# Other.net
KiCad netlist of a schematic drawn in Altium Designer
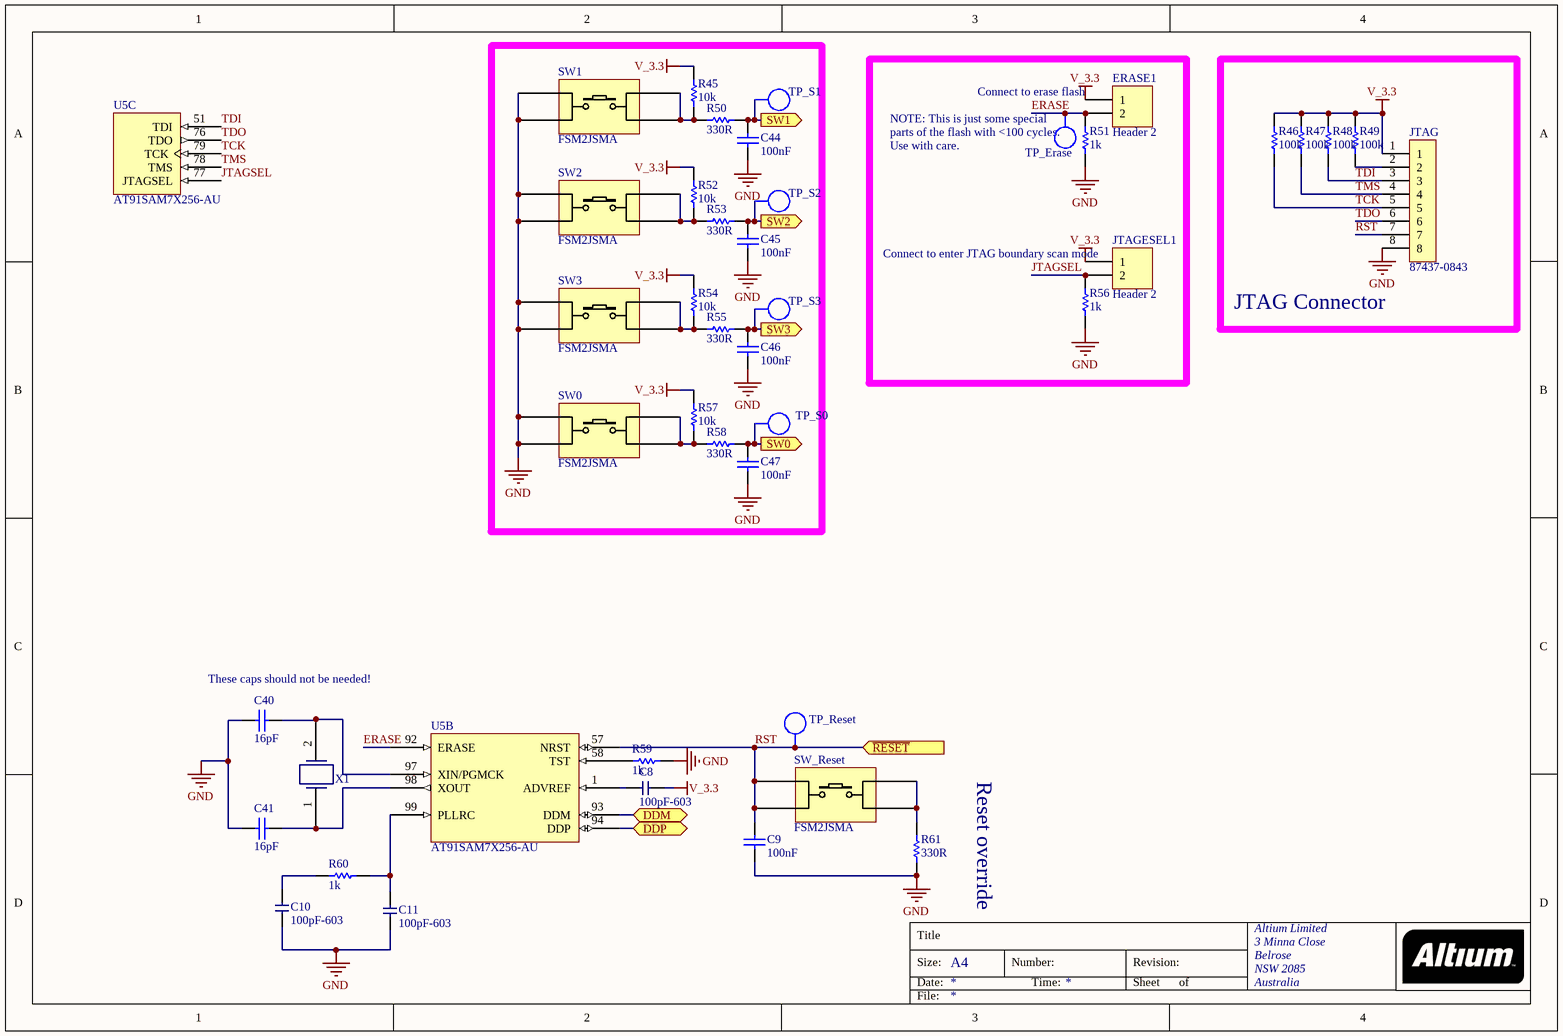
[diagram p0: Other.SchDoc]

(export (version "E")
  (design (tool "Eeschema 10.0.6"))
  (components
    (comp (ref "C8")
      (value "100pF-603")
      (footprint "0603 Resistor")
      (fields
        (field (name "MANUFACTURER PART NUMBER") "06035A101JAT2A")
        (field (name "MANUFACTURER") "AVX Corporation")
      )
      (libsource (lib "MarioLib") (part "100pF-603"))
    )
    (comp (ref "C9")
      (value "100nF")
      (footprint "0603")
      (description "CAP CER .10UF 50V X5R 0603")
      (fields (field (name "PART NUMBER") "CP_100nF 0603") (field (name "MANUFACTURER") "Taiyo Yuden"))
      (libsource (lib "ENEL429_4") (part "CP_100nF 0603"))
    )
    (comp (ref "C10")
      (value "100pF-603")
      (footprint "0603 Resistor")
      (fields
        (field (name "MANUFACTURER PART NUMBER") "06035A101JAT2A")
        (field (name "MANUFACTURER") "AVX Corporation")
      )
      (libsource (lib "MarioLib") (part "100pF-603"))
    )
    (comp (ref "C11")
      (value "100pF-603")
      (footprint "0603 Resistor")
      (fields
        (field (name "MANUFACTURER PART NUMBER") "06035A101JAT2A")
        (field (name "MANUFACTURER") "AVX Corporation")
      )
      (libsource (lib "MarioLib") (part "100pF-603"))
    )
    (comp (ref "C40")
      (value "16pF")
      (footprint "0603")
      (description "CAP CER 16PF 100V 5% C0G 0603")
      (fields (field (name "MANUFACTURER") "Murata") (field (name "PART NUMBER") "CP_16pF_100V_0603"))
      (libsource (lib "ENEL429_4") (part "CP_16pF_100V_0603"))
    )
    (comp (ref "C41")
      (value "16pF")
      (footprint "0603")
      (description "CAP CER 16PF 100V 5% C0G 0603")
      (fields (field (name "MANUFACTURER") "Murata") (field (name "PART NUMBER") "CP_16pF_100V_0603"))
      (libsource (lib "ENEL429_4") (part "CP_16pF_100V_0603"))
    )
    (comp (ref "C44")
      (value "100nF")
      (footprint "0603")
      (description "CAP CER .10UF 50V X5R 0603")
      (fields (field (name "MANUFACTURER") "Taiyo Yuden") (field (name "PART NUMBER") "CP_100nF 0603"))
      (libsource (lib "ENEL429_4") (part "CP_100nF 0603"))
    )
    (comp (ref "C45")
      (value "100nF")
      (footprint "0603")
      (description "CAP CER .10UF 50V X5R 0603")
      (fields (field (name "MANUFACTURER") "Taiyo Yuden") (field (name "PART NUMBER") "CP_100nF 0603"))
      (libsource (lib "ENEL429_4") (part "CP_100nF 0603"))
    )
    (comp (ref "C46")
      (value "100nF")
      (footprint "0603")
      (description "CAP CER .10UF 50V X5R 0603")
      (fields (field (name "MANUFACTURER") "Taiyo Yuden") (field (name "PART NUMBER") "CP_100nF 0603"))
      (libsource (lib "ENEL429_4") (part "CP_100nF 0603"))
    )
    (comp (ref "C47")
      (value "100nF")
      (footprint "0603")
      (description "CAP CER .10UF 50V X5R 0603")
      (fields (field (name "MANUFACTURER") "Taiyo Yuden") (field (name "PART NUMBER") "CP_100nF 0603"))
      (libsource (lib "ENEL429_4") (part "CP_100nF 0603"))
    )
    (comp (ref "ERASE1")
      (value "Header 2")
      (footprint "HDR1X2")
      (description "Header, 2-Pin")
      (fields (field (name "PUBLISHER") "Altium Limited"))
      (libsource (lib "Miscellaneous Connectors") (part "Header 2"))
    )
    (comp (ref "JTAG")
      (value "87437-0843")
      (footprint "87437-0843")
      (fields (field (name "MANUFACTURER") "Molex"))
      (libsource (lib "MarioLib") (part "87437-0843"))
    )
    (comp (ref "JTAGESEL1")
      (value "Header 2")
      (footprint "HDR1X2")
      (description "Header, 2-Pin")
      (fields (field (name "PUBLISHER") "Altium Limited"))
      (libsource (lib "Miscellaneous Connectors") (part "Header 2"))
    )
    (comp (ref "R45")
      (value "10k")
      (footprint "0603")
      (description "RES 10.0K OHM 1/10W 1% 0603 SMD")
      (fields (field (name "MANUFACTURER") "Yageo") (field (name "PART NUMBER") "RS_10k 0603"))
      (libsource (lib "ENEL429_4") (part "RS_10k 0603"))
    )
    (comp (ref "R46")
      (value "100k")
      (footprint "0603")
      (description "RES 100K OHM 1/10W 1% 0603 SMD")
      (fields (field (name "PART NUMBER") "RS_100k 0603") (field (name "MANUFACTURER") "Yageo"))
      (libsource (lib "ENEL429_4") (part "RS_100k 0603"))
    )
    (comp (ref "R47")
      (value "100k")
      (footprint "0603")
      (description "RES 100K OHM 1/10W 1% 0603 SMD")
      (fields (field (name "PART NUMBER") "RS_100k 0603") (field (name "MANUFACTURER") "Yageo"))
      (libsource (lib "ENEL429_4") (part "RS_100k 0603"))
    )
    (comp (ref "R48")
      (value "100k")
      (footprint "0603")
      (description "RES 100K OHM 1/10W 1% 0603 SMD")
      (fields (field (name "PART NUMBER") "RS_100k 0603") (field (name "MANUFACTURER") "Yageo"))
      (libsource (lib "ENEL429_4") (part "RS_100k 0603"))
    )
    (comp (ref "R49")
      (value "100k")
      (footprint "0603")
      (description "RES 100K OHM 1/10W 1% 0603 SMD")
      (fields (field (name "PART NUMBER") "RS_100k 0603") (field (name "MANUFACTURER") "Yageo"))
      (libsource (lib "ENEL429_4") (part "RS_100k 0603"))
    )
    (comp (ref "R50")
      (value "330R")
      (footprint "0603")
      (description "RES 330 OHM 1/10W 1% 0603 SMD")
      (fields (field (name "MANUFACTURER") "Yageo") (field (name "PART NUMBER") "RS_330R 0603"))
      (libsource (lib "ENEL429_4") (part "RS_330R 0603"))
    )
    (comp (ref "R51")
      (value "1k")
      (footprint "0603")
      (description "RES 1.00K OHM 1/10W 1% 0603 SMD")
      (fields (field (name "PART NUMBER") "RS_1k 0603") (field (name "MANUFACTURER") "ROHM"))
      (libsource (lib "ENEL429_4") (part "RS_1k 0603"))
    )
    (comp (ref "R52")
      (value "10k")
      (footprint "0603")
      (description "RES 10.0K OHM 1/10W 1% 0603 SMD")
      (fields (field (name "MANUFACTURER") "Yageo") (field (name "PART NUMBER") "RS_10k 0603"))
      (libsource (lib "ENEL429_4") (part "RS_10k 0603"))
    )
    (comp (ref "R53")
      (value "330R")
      (footprint "0603")
      (description "RES 330 OHM 1/10W 1% 0603 SMD")
      (fields (field (name "MANUFACTURER") "Yageo") (field (name "PART NUMBER") "RS_330R 0603"))
      (libsource (lib "ENEL429_4") (part "RS_330R 0603"))
    )
    (comp (ref "R54")
      (value "10k")
      (footprint "0603")
      (description "RES 10.0K OHM 1/10W 1% 0603 SMD")
      (fields (field (name "MANUFACTURER") "Yageo") (field (name "PART NUMBER") "RS_10k 0603"))
      (libsource (lib "ENEL429_4") (part "RS_10k 0603"))
    )
    (comp (ref "R55")
      (value "330R")
      (footprint "0603")
      (description "RES 330 OHM 1/10W 1% 0603 SMD")
      (fields (field (name "MANUFACTURER") "Yageo") (field (name "PART NUMBER") "RS_330R 0603"))
      (libsource (lib "ENEL429_4") (part "RS_330R 0603"))
    )
    (comp (ref "R56")
      (value "1k")
      (footprint "0603")
      (description "RES 1.00K OHM 1/10W 1% 0603 SMD")
      (fields (field (name "PART NUMBER") "RS_1k 0603") (field (name "MANUFACTURER") "ROHM"))
      (libsource (lib "ENEL429_4") (part "RS_1k 0603"))
    )
    (comp (ref "R57")
      (value "10k")
      (footprint "0603")
      (description "RES 10.0K OHM 1/10W 1% 0603 SMD")
      (fields (field (name "MANUFACTURER") "Yageo") (field (name "PART NUMBER") "RS_10k 0603"))
      (libsource (lib "ENEL429_4") (part "RS_10k 0603"))
    )
    (comp (ref "R58")
      (value "330R")
      (footprint "0603")
      (description "RES 330 OHM 1/10W 1% 0603 SMD")
      (fields (field (name "MANUFACTURER") "Yageo") (field (name "PART NUMBER") "RS_330R 0603"))
      (libsource (lib "ENEL429_4") (part "RS_330R 0603"))
    )
    (comp (ref "R59")
      (value "1k")
      (footprint "0603")
      (description "RES 1.00K OHM 1/10W 1% 0603 SMD")
      (fields (field (name "PART NUMBER") "RS_1k 0603") (field (name "MANUFACTURER") "ROHM"))
      (libsource (lib "ENEL429_4") (part "RS_1k 0603"))
    )
    (comp (ref "R60")
      (value "1k")
      (footprint "0603")
      (description "RES 1.00K OHM 1/10W 1% 0603 SMD")
      (fields (field (name "MANUFACTURER") "ROHM") (field (name "PART NUMBER") "RS_1k 0603"))
      (libsource (lib "ENEL429_4") (part "RS_1k 0603"))
    )
    (comp (ref "R61")
      (value "330R")
      (footprint "0603")
      (description "RES 330 OHM 1/10W 1% 0603 SMD")
      (fields (field (name "PART NUMBER") "RS_330R 0603") (field (name "MANUFACTURER") "Yageo"))
      (libsource (lib "ENEL429_4") (part "RS_330R 0603"))
    )
    (comp (ref "SW0")
      (value "FSM2JSMA")
      (footprint "FSM2JSMA")
      (description "DPST SMD Switch")
      (fields (field (name "MANUFACTURER") "Tyco Electronics") (field (name "PART NUMBER") "SW_FSM2JSMA"))
      (libsource (lib "ENEL429_4") (part "SW_FSM2JSMA"))
    )
    (comp (ref "SW1")
      (value "FSM2JSMA")
      (footprint "FSM2JSMA")
      (description "DPST SMD Switch")
      (fields (field (name "MANUFACTURER") "Tyco Electronics") (field (name "PART NUMBER") "SW_FSM2JSMA"))
      (libsource (lib "ENEL429_4") (part "SW_FSM2JSMA"))
    )
    (comp (ref "SW2")
      (value "FSM2JSMA")
      (footprint "FSM2JSMA")
      (description "DPST SMD Switch")
      (fields (field (name "MANUFACTURER") "Tyco Electronics") (field (name "PART NUMBER") "SW_FSM2JSMA"))
      (libsource (lib "ENEL429_4") (part "SW_FSM2JSMA"))
    )
    (comp (ref "SW3")
      (value "FSM2JSMA")
      (footprint "FSM2JSMA")
      (description "DPST SMD Switch")
      (fields (field (name "MANUFACTURER") "Tyco Electronics") (field (name "PART NUMBER") "SW_FSM2JSMA"))
      (libsource (lib "ENEL429_4") (part "SW_FSM2JSMA"))
    )
    (comp (ref "SW_Reset")
      (value "FSM2JSMA")
      (footprint "FSM2JSMA")
      (description "DPST SMD Switch")
      (fields (field (name "MANUFACTURER") "Tyco Electronics") (field (name "PART NUMBER") "SW_FSM2JSMA"))
      (libsource (lib "ENEL429_4") (part "SW_FSM2JSMA"))
    )
    (comp (ref "TP_Erase")
      (value "TP")
      (footprint "TEST_POINT_4X2MM")
      (description "Test-Point")
      (fields (field (name "PART NUMBER") "TP_TESTPOINT"))
      (libsource (lib "ENEL429_4") (part "TP_TESTPOINT"))
    )
    (comp (ref "TP_Reset")
      (value "TP")
      (footprint "TEST_POINT_4X2MM")
      (description "Test-Point")
      (fields (field (name "PART NUMBER") "TP_TESTPOINT"))
      (libsource (lib "ENEL429_4") (part "TP_TESTPOINT"))
    )
    (comp (ref "TP_S0")
      (value "TP")
      (footprint "TEST_POINT_4X2MM")
      (description "Test-Point")
      (fields (field (name "PART NUMBER") "TP_TESTPOINT"))
      (libsource (lib "ENEL429_4") (part "TP_TESTPOINT"))
    )
    (comp (ref "TP_S1")
      (value "TP")
      (footprint "TEST_POINT_4X2MM")
      (description "Test-Point")
      (fields (field (name "PART NUMBER") "TP_TESTPOINT"))
      (libsource (lib "ENEL429_4") (part "TP_TESTPOINT"))
    )
    (comp (ref "TP_S2")
      (value "TP")
      (footprint "TEST_POINT_4X2MM")
      (description "Test-Point")
      (fields (field (name "PART NUMBER") "TP_TESTPOINT"))
      (libsource (lib "ENEL429_4") (part "TP_TESTPOINT"))
    )
    (comp (ref "TP_S3")
      (value "TP")
      (footprint "TEST_POINT_4X2MM")
      (description "Test-Point")
      (fields (field (name "PART NUMBER") "TP_TESTPOINT"))
      (libsource (lib "ENEL429_4") (part "TP_TESTPOINT"))
    )
    (comp (ref "U5")
      (value "AT91SAM7X256-AU")
      (footprint "LQFP100_N")
      (fields (field (name "PUBLISHER") "Altium Limited"))
      (libsource (lib "Atmel Microcontroller 32-Bit ARM") (part "AT91SAM7X256-AU"))
    )
    (comp (ref "X1")
      (value "ECS-184-20-5PXDU-TR")
      (footprint "HC49/US")
      (fields (field (name "MANUFACTURER") "ECS Inc"))
      (libsource (lib "MarioLib") (part "ECS-184-20-5PXDU-TR"))
    )
  )
  (nets
    (net (code "1") (name "/DDM") (class "Default")
      (node (ref "U5") (pin "93") (pinfunction "DDM_93") (pintype "bidirectional"))
    )
    (net (code "2") (name "/DDP") (class "Default")
      (node (ref "U5") (pin "94") (pinfunction "DDP_94") (pintype "bidirectional"))
    )
    (net (code "3") (name "/ERASE") (class "Default")
      (node (ref "ERASE1") (pin "2") (pinfunction "2_2") (pintype "passive"))
      (node (ref "R51") (pin "2") (pinfunction "2_2") (pintype "passive"))
      (node (ref "TP_Erase") (pin "1") (pinfunction "1_1") (pintype "passive"))
      (node (ref "U5") (pin "92") (pinfunction "ERASE_92") (pintype "input"))
    )
    (net (code "4") (name "/JTAGSEL") (class "Default")
      (node (ref "JTAGESEL1") (pin "2") (pinfunction "2_2") (pintype "passive"))
      (node (ref "R56") (pin "2") (pinfunction "2_2") (pintype "passive"))
      (node (ref "U5") (pin "77") (pinfunction "JTAGSEL_77") (pintype "input"))
    )
    (net (code "5") (name "/RST") (class "Default")
      (node (ref "C9") (pin "1") (pinfunction "1_1") (pintype "passive"))
      (node (ref "JTAG") (pin "7") (pinfunction "7_7") (pintype "passive"))
      (node (ref "SW_Reset") (pin "1") (pinfunction "1_1") (pintype "passive"))
      (node (ref "SW_Reset") (pin "2") (pinfunction "2_2") (pintype "passive"))
      (node (ref "TP_Reset") (pin "1") (pinfunction "1_1") (pintype "passive"))
      (node (ref "U5") (pin "57") (pinfunction "NRST_57") (pintype "bidirectional"))
    )
    (net (code "6") (name "/SW0") (class "Default")
      (node (ref "C47") (pin "2") (pinfunction "2_2") (pintype "passive"))
      (node (ref "R58") (pin "2") (pinfunction "2_2") (pintype "passive"))
      (node (ref "TP_S0") (pin "1") (pinfunction "1_1") (pintype "passive"))
    )
    (net (code "7") (name "/SW1") (class "Default")
      (node (ref "C44") (pin "2") (pinfunction "2_2") (pintype "passive"))
      (node (ref "R50") (pin "2") (pinfunction "2_2") (pintype "passive"))
      (node (ref "TP_S1") (pin "1") (pinfunction "1_1") (pintype "passive"))
    )
    (net (code "8") (name "/SW2") (class "Default")
      (node (ref "C45") (pin "2") (pinfunction "2_2") (pintype "passive"))
      (node (ref "R53") (pin "2") (pinfunction "2_2") (pintype "passive"))
      (node (ref "TP_S2") (pin "1") (pinfunction "1_1") (pintype "passive"))
    )
    (net (code "9") (name "/SW3") (class "Default")
      (node (ref "C46") (pin "2") (pinfunction "2_2") (pintype "passive"))
      (node (ref "R55") (pin "2") (pinfunction "2_2") (pintype "passive"))
      (node (ref "TP_S3") (pin "1") (pinfunction "1_1") (pintype "passive"))
    )
    (net (code "10") (name "/TCK") (class "Default")
      (node (ref "JTAG") (pin "5") (pinfunction "5_5") (pintype "passive"))
      (node (ref "R46") (pin "2") (pinfunction "2_2") (pintype "passive"))
      (node (ref "U5") (pin "79") (pinfunction "TCK_79") (pintype "input"))
    )
    (net (code "11") (name "/TDI") (class "Default")
      (node (ref "JTAG") (pin "3") (pinfunction "3_3") (pintype "passive"))
      (node (ref "R48") (pin "2") (pinfunction "2_2") (pintype "passive"))
      (node (ref "U5") (pin "51") (pinfunction "TDI_51") (pintype "input"))
    )
    (net (code "12") (name "/TDO") (class "Default")
      (node (ref "JTAG") (pin "6") (pinfunction "6_6") (pintype "passive"))
      (node (ref "U5") (pin "76") (pinfunction "TDO_76") (pintype "output"))
    )
    (net (code "13") (name "/TMS") (class "Default")
      (node (ref "JTAG") (pin "4") (pinfunction "4_4") (pintype "passive"))
      (node (ref "R47") (pin "2") (pinfunction "2_2") (pintype "passive"))
      (node (ref "U5") (pin "78") (pinfunction "TMS_78") (pintype "input"))
    )
    (net (code "14") (name "GND") (class "Default")
      (node (ref "C10") (pin "1") (pinfunction "1_1") (pintype "passive"))
      (node (ref "C11") (pin "1") (pinfunction "1_1") (pintype "passive"))
      (node (ref "C40") (pin "1") (pinfunction "1_1") (pintype "passive"))
      (node (ref "C41") (pin "2") (pinfunction "2_2") (pintype "passive"))
      (node (ref "C44") (pin "1") (pinfunction "1_1") (pintype "passive"))
      (node (ref "C45") (pin "1") (pinfunction "1_1") (pintype "passive"))
      (node (ref "C46") (pin "1") (pinfunction "1_1") (pintype "passive"))
      (node (ref "C47") (pin "1") (pinfunction "1_1") (pintype "passive"))
      (node (ref "C9") (pin "2") (pinfunction "2_2") (pintype "passive"))
      (node (ref "JTAG") (pin "8") (pinfunction "8_8") (pintype "passive"))
      (node (ref "R51") (pin "1") (pinfunction "1_1") (pintype "passive"))
      (node (ref "R56") (pin "1") (pinfunction "1_1") (pintype "passive"))
      (node (ref "R59") (pin "1") (pinfunction "1_1") (pintype "passive"))
      (node (ref "R61") (pin "1") (pinfunction "1_1") (pintype "passive"))
      (node (ref "SW0") (pin "1") (pinfunction "1_1") (pintype "passive"))
      (node (ref "SW0") (pin "2") (pinfunction "2_2") (pintype "passive"))
      (node (ref "SW1") (pin "1") (pinfunction "1_1") (pintype "passive"))
      (node (ref "SW1") (pin "2") (pinfunction "2_2") (pintype "passive"))
      (node (ref "SW2") (pin "1") (pinfunction "1_1") (pintype "passive"))
      (node (ref "SW2") (pin "2") (pinfunction "2_2") (pintype "passive"))
      (node (ref "SW3") (pin "1") (pinfunction "1_1") (pintype "passive"))
      (node (ref "SW3") (pin "2") (pinfunction "2_2") (pintype "passive"))
    )
    (net (code "15") (name "Net-(C10-Pad2)") (class "Default")
      (node (ref "C10") (pin "2") (pinfunction "2_2") (pintype "passive"))
      (node (ref "R60") (pin "1") (pinfunction "1_1") (pintype "passive"))
    )
    (net (code "16") (name "Net-(JTAG-Pad2)") (class "Default")
      (node (ref "JTAG") (pin "2") (pinfunction "2_2") (pintype "passive"))
      (node (ref "R49") (pin "2") (pinfunction "2_2") (pintype "passive"))
    )
    (net (code "17") (name "Net-(R45-Pad1)") (class "Default")
      (node (ref "R45") (pin "1") (pinfunction "1_1") (pintype "passive"))
      (node (ref "R50") (pin "1") (pinfunction "1_1") (pintype "passive"))
      (node (ref "SW1") (pin "3") (pinfunction "3_3") (pintype "passive"))
      (node (ref "SW1") (pin "4") (pinfunction "4_4") (pintype "passive"))
    )
    (net (code "18") (name "Net-(R52-Pad1)") (class "Default")
      (node (ref "R52") (pin "1") (pinfunction "1_1") (pintype "passive"))
      (node (ref "R53") (pin "1") (pinfunction "1_1") (pintype "passive"))
      (node (ref "SW2") (pin "3") (pinfunction "3_3") (pintype "passive"))
      (node (ref "SW2") (pin "4") (pinfunction "4_4") (pintype "passive"))
    )
    (net (code "19") (name "Net-(R54-Pad1)") (class "Default")
      (node (ref "R54") (pin "1") (pinfunction "1_1") (pintype "passive"))
      (node (ref "R55") (pin "1") (pinfunction "1_1") (pintype "passive"))
      (node (ref "SW3") (pin "3") (pinfunction "3_3") (pintype "passive"))
      (node (ref "SW3") (pin "4") (pinfunction "4_4") (pintype "passive"))
    )
    (net (code "20") (name "Net-(R57-Pad1)") (class "Default")
      (node (ref "R57") (pin "1") (pinfunction "1_1") (pintype "passive"))
      (node (ref "R58") (pin "1") (pinfunction "1_1") (pintype "passive"))
      (node (ref "SW0") (pin "3") (pinfunction "3_3") (pintype "passive"))
      (node (ref "SW0") (pin "4") (pinfunction "4_4") (pintype "passive"))
    )
    (net (code "21") (name "Net-(R61-Pad2)") (class "Default")
      (node (ref "R61") (pin "2") (pinfunction "2_2") (pintype "passive"))
      (node (ref "SW_Reset") (pin "3") (pinfunction "3_3") (pintype "passive"))
      (node (ref "SW_Reset") (pin "4") (pinfunction "4_4") (pintype "passive"))
    )
    (net (code "22") (name "Net-(U5B-ADVREF)") (class "Default")
      (node (ref "C8") (pin "1") (pinfunction "1_1") (pintype "passive"))
      (node (ref "U5") (pin "1") (pinfunction "ADVREF_1") (pintype "input"))
    )
    (net (code "23") (name "Net-(U5B-PLLRC)") (class "Default")
      (node (ref "C11") (pin "2") (pinfunction "2_2") (pintype "passive"))
      (node (ref "R60") (pin "2") (pinfunction "2_2") (pintype "passive"))
      (node (ref "U5") (pin "99") (pinfunction "PLLRC_99") (pintype "input"))
    )
    (net (code "24") (name "Net-(U5B-TST)") (class "Default")
      (node (ref "R59") (pin "2") (pinfunction "2_2") (pintype "passive"))
      (node (ref "U5") (pin "58") (pinfunction "TST_58") (pintype "input"))
    )
    (net (code "25") (name "Net-(U5B-XIN{slash}PGMCK)") (class "Default")
      (node (ref "C40") (pin "2") (pinfunction "2_2") (pintype "passive"))
      (node (ref "U5") (pin "97") (pinfunction "XIN/PGMCK_97") (pintype "input"))
      (node (ref "X1") (pin "2") (pinfunction "19_2") (pintype "passive"))
    )
    (net (code "26") (name "Net-(U5B-XOUT)") (class "Default")
      (node (ref "C41") (pin "1") (pinfunction "1_1") (pintype "passive"))
      (node (ref "U5") (pin "98") (pinfunction "XOUT_98") (pintype "output"))
      (node (ref "X1") (pin "1") (pinfunction "18_1") (pintype "passive"))
    )
    (net (code "27") (name "V_3.3") (class "Default")
      (node (ref "C8") (pin "2") (pinfunction "2_2") (pintype "passive"))
      (node (ref "ERASE1") (pin "1") (pinfunction "1_1") (pintype "passive"))
      (node (ref "JTAG") (pin "1") (pinfunction "1_1") (pintype "passive"))
      (node (ref "JTAGESEL1") (pin "1") (pinfunction "1_1") (pintype "passive"))
      (node (ref "R45") (pin "2") (pinfunction "2_2") (pintype "passive"))
      (node (ref "R46") (pin "1") (pinfunction "1_1") (pintype "passive"))
      (node (ref "R47") (pin "1") (pinfunction "1_1") (pintype "passive"))
      (node (ref "R48") (pin "1") (pinfunction "1_1") (pintype "passive"))
      (node (ref "R49") (pin "1") (pinfunction "1_1") (pintype "passive"))
      (node (ref "R52") (pin "2") (pinfunction "2_2") (pintype "passive"))
      (node (ref "R54") (pin "2") (pinfunction "2_2") (pintype "passive"))
      (node (ref "R57") (pin "2") (pinfunction "2_2") (pintype "passive"))
    )
  )
)
